# PSU-Board-V2-0.net
KiCad netlist of a schematic drawn in EAGLE
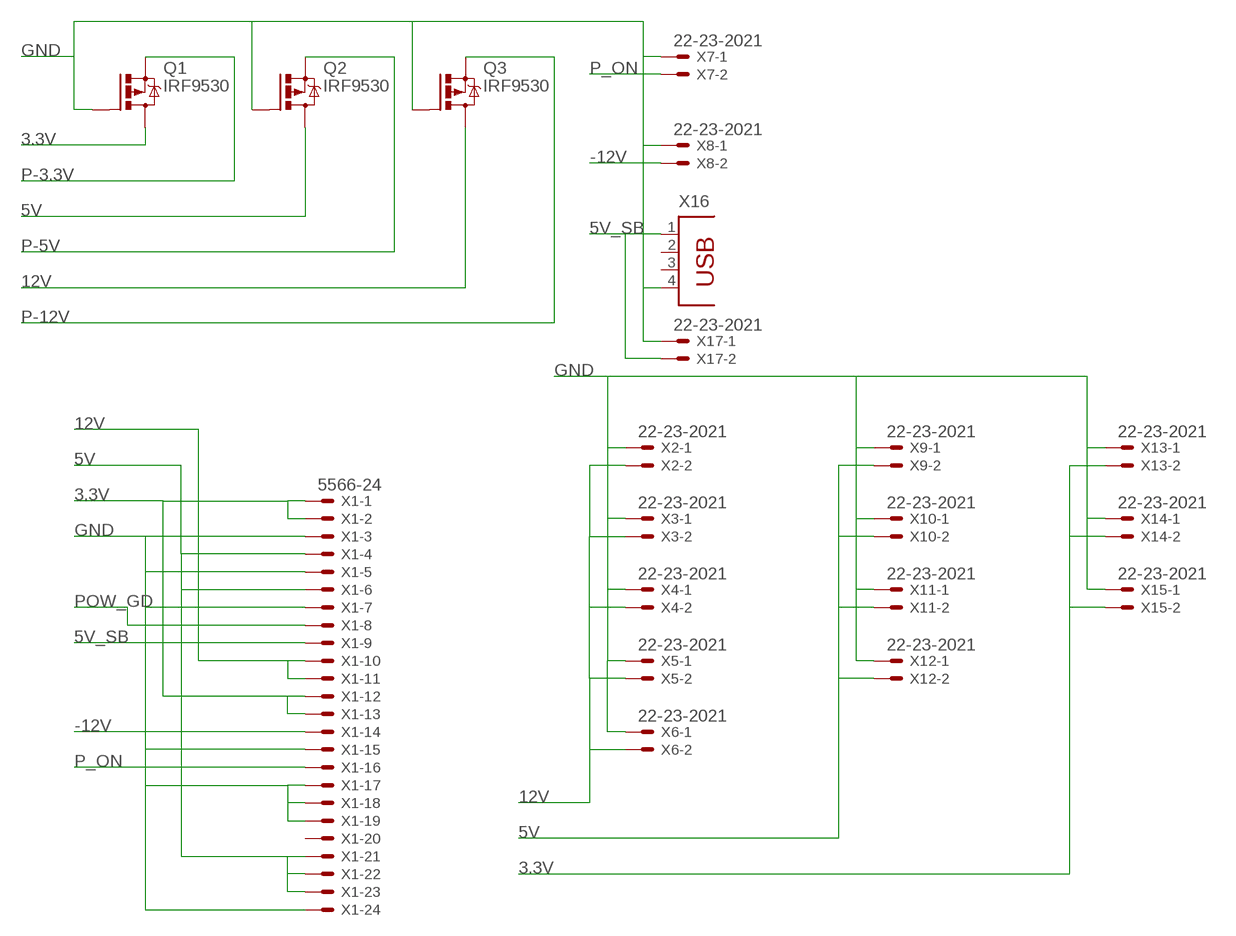
[diagram p0: schematic, sheet 1]

(export (version "E")
  (design (tool "Eeschema 10.0.6"))
  (components
    (comp (ref "Q1")
      (value "IRF9530")
      (footprint "eagle-import:TO220BV")
      (libsource (lib "eagle-import") (part "IRF9530"))
    )
    (comp (ref "Q2")
      (value "IRF9530")
      (footprint "eagle-import:TO220BV")
      (libsource (lib "eagle-import") (part "IRF9530"))
    )
    (comp (ref "Q3")
      (value "IRF9530")
      (footprint "eagle-import:TO220BV")
      (libsource (lib "eagle-import") (part "IRF9530"))
    )
    (comp (ref "X1")
      (value "5566-24")
      (footprint "eagle-import:5566-24")
      (libsource (lib "eagle-import") (part "5566-24"))
    )
    (comp (ref "X2")
      (value "22-23-2021")
      (footprint "eagle-import:22-23-2021")
      (fields (field (name "MF") "MOLEX"))
      (libsource (lib "eagle-import") (part "22-23-2021"))
    )
    (comp (ref "X3")
      (value "22-23-2021")
      (footprint "eagle-import:22-23-2021")
      (fields (field (name "MF") "MOLEX"))
      (libsource (lib "eagle-import") (part "22-23-2021"))
    )
    (comp (ref "X4")
      (value "22-23-2021")
      (footprint "eagle-import:22-23-2021")
      (fields (field (name "MF") "MOLEX"))
      (libsource (lib "eagle-import") (part "22-23-2021"))
    )
    (comp (ref "X5")
      (value "22-23-2021")
      (footprint "eagle-import:22-23-2021")
      (fields (field (name "MF") "MOLEX"))
      (libsource (lib "eagle-import") (part "22-23-2021"))
    )
    (comp (ref "X6")
      (value "22-23-2021")
      (footprint "eagle-import:22-23-2021")
      (fields (field (name "MF") "MOLEX"))
      (libsource (lib "eagle-import") (part "22-23-2021"))
    )
    (comp (ref "X7")
      (value "22-23-2021")
      (footprint "eagle-import:22-23-2021")
      (fields (field (name "MF") "MOLEX"))
      (libsource (lib "eagle-import") (part "22-23-2021"))
    )
    (comp (ref "X8")
      (value "22-23-2021")
      (footprint "eagle-import:22-23-2021")
      (fields (field (name "MF") "MOLEX"))
      (libsource (lib "eagle-import") (part "22-23-2021"))
    )
    (comp (ref "X9")
      (value "22-23-2021")
      (footprint "eagle-import:22-23-2021")
      (fields (field (name "MF") "MOLEX"))
      (libsource (lib "eagle-import") (part "22-23-2021"))
    )
    (comp (ref "X10")
      (value "22-23-2021")
      (footprint "eagle-import:22-23-2021")
      (fields (field (name "MF") "MOLEX"))
      (libsource (lib "eagle-import") (part "22-23-2021"))
    )
    (comp (ref "X11")
      (value "22-23-2021")
      (footprint "eagle-import:22-23-2021")
      (fields (field (name "MF") "MOLEX"))
      (libsource (lib "eagle-import") (part "22-23-2021"))
    )
    (comp (ref "X12")
      (value "22-23-2021")
      (footprint "eagle-import:22-23-2021")
      (fields (field (name "MF") "MOLEX"))
      (libsource (lib "eagle-import") (part "22-23-2021"))
    )
    (comp (ref "X13")
      (value "22-23-2021")
      (footprint "eagle-import:22-23-2021")
      (fields (field (name "MF") "MOLEX"))
      (libsource (lib "eagle-import") (part "22-23-2021"))
    )
    (comp (ref "X14")
      (value "22-23-2021")
      (footprint "eagle-import:22-23-2021")
      (fields (field (name "MF") "MOLEX"))
      (libsource (lib "eagle-import") (part "22-23-2021"))
    )
    (comp (ref "X15")
      (value "22-23-2021")
      (footprint "eagle-import:22-23-2021")
      (fields (field (name "MF") "MOLEX"))
      (libsource (lib "eagle-import") (part "22-23-2021"))
    )
    (comp (ref "X16")
      (value "PN87520")
      (footprint "eagle-import:PN87520")
      (libsource (lib "eagle-import") (part "PN87520"))
    )
    (comp (ref "X17")
      (value "22-23-2021")
      (footprint "eagle-import:22-23-2021")
      (fields (field (name "MF") "MOLEX"))
      (libsource (lib "eagle-import") (part "22-23-2021"))
    )
  )
  (nets
    (net (code "1") (name "/-12V") (class "Default")
      (node (ref "X1") (pin "14") (pinfunction "S_14") (pintype "passive"))
      (node (ref "X8") (pin "2") (pinfunction "S_2") (pintype "passive"))
    )
    (net (code "2") (name "/3.3V") (class "Default")
      (node (ref "Q1") (pin "D") (pinfunction "D_D") (pintype "passive"))
      (node (ref "X1") (pin "1") (pinfunction "S_1") (pintype "passive"))
      (node (ref "X1") (pin "12") (pinfunction "S_12") (pintype "passive"))
      (node (ref "X1") (pin "13") (pinfunction "S_13") (pintype "passive"))
      (node (ref "X1") (pin "2") (pinfunction "S_2") (pintype "passive"))
      (node (ref "X13") (pin "2") (pinfunction "S_2") (pintype "passive"))
      (node (ref "X14") (pin "2") (pinfunction "S_2") (pintype "passive"))
      (node (ref "X15") (pin "2") (pinfunction "S_2") (pintype "passive"))
    )
    (net (code "3") (name "/5V") (class "Default")
      (node (ref "Q2") (pin "D") (pinfunction "D_D") (pintype "passive"))
      (node (ref "X1") (pin "21") (pinfunction "S_21") (pintype "passive"))
      (node (ref "X1") (pin "22") (pinfunction "S_22") (pintype "passive"))
      (node (ref "X1") (pin "23") (pinfunction "S_23") (pintype "passive"))
      (node (ref "X1") (pin "4") (pinfunction "S_4") (pintype "passive"))
      (node (ref "X1") (pin "6") (pinfunction "S_6") (pintype "passive"))
      (node (ref "X10") (pin "2") (pinfunction "S_2") (pintype "passive"))
      (node (ref "X11") (pin "2") (pinfunction "S_2") (pintype "passive"))
      (node (ref "X12") (pin "2") (pinfunction "S_2") (pintype "passive"))
      (node (ref "X9") (pin "2") (pinfunction "S_2") (pintype "passive"))
    )
    (net (code "4") (name "/5V_SB") (class "Default")
      (node (ref "X1") (pin "9") (pinfunction "S_9") (pintype "passive"))
      (node (ref "X16") (pin "1") (pinfunction "1_1") (pintype "passive"))
      (node (ref "X17") (pin "2") (pinfunction "S_2") (pintype "passive"))
    )
    (net (code "5") (name "/12V") (class "Default")
      (node (ref "Q3") (pin "D") (pinfunction "D_D") (pintype "passive"))
      (node (ref "X1") (pin "10") (pinfunction "S_10") (pintype "passive"))
      (node (ref "X1") (pin "11") (pinfunction "S_11") (pintype "passive"))
      (node (ref "X2") (pin "2") (pinfunction "S_2") (pintype "passive"))
      (node (ref "X3") (pin "2") (pinfunction "S_2") (pintype "passive"))
      (node (ref "X4") (pin "2") (pinfunction "S_2") (pintype "passive"))
      (node (ref "X5") (pin "2") (pinfunction "S_2") (pintype "passive"))
      (node (ref "X6") (pin "2") (pinfunction "S_2") (pintype "passive"))
    )
    (net (code "6") (name "/GND") (class "Default")
      (node (ref "Q1") (pin "G") (pinfunction "G_G") (pintype "passive"))
      (node (ref "Q2") (pin "G") (pinfunction "G_G") (pintype "passive"))
      (node (ref "Q3") (pin "G") (pinfunction "G_G") (pintype "passive"))
      (node (ref "X1") (pin "15") (pinfunction "S_15") (pintype "passive"))
      (node (ref "X1") (pin "17") (pinfunction "S_17") (pintype "passive"))
      (node (ref "X1") (pin "18") (pinfunction "S_18") (pintype "passive"))
      (node (ref "X1") (pin "19") (pinfunction "S_19") (pintype "passive"))
      (node (ref "X1") (pin "24") (pinfunction "S_24") (pintype "passive"))
      (node (ref "X1") (pin "3") (pinfunction "S_3") (pintype "passive"))
      (node (ref "X1") (pin "5") (pinfunction "S_5") (pintype "passive"))
      (node (ref "X1") (pin "7") (pinfunction "S_7") (pintype "passive"))
      (node (ref "X10") (pin "1") (pinfunction "S_1") (pintype "passive"))
      (node (ref "X11") (pin "1") (pinfunction "S_1") (pintype "passive"))
      (node (ref "X12") (pin "1") (pinfunction "S_1") (pintype "passive"))
      (node (ref "X13") (pin "1") (pinfunction "S_1") (pintype "passive"))
      (node (ref "X14") (pin "1") (pinfunction "S_1") (pintype "passive"))
      (node (ref "X15") (pin "1") (pinfunction "S_1") (pintype "passive"))
      (node (ref "X16") (pin "4") (pinfunction "4_4") (pintype "passive"))
      (node (ref "X17") (pin "1") (pinfunction "S_1") (pintype "passive"))
      (node (ref "X2") (pin "1") (pinfunction "S_1") (pintype "passive"))
      (node (ref "X3") (pin "1") (pinfunction "S_1") (pintype "passive"))
      (node (ref "X4") (pin "1") (pinfunction "S_1") (pintype "passive"))
      (node (ref "X5") (pin "1") (pinfunction "S_1") (pintype "passive"))
      (node (ref "X6") (pin "1") (pinfunction "S_1") (pintype "passive"))
      (node (ref "X7") (pin "1") (pinfunction "S_1") (pintype "passive"))
      (node (ref "X8") (pin "1") (pinfunction "S_1") (pintype "passive"))
      (node (ref "X9") (pin "1") (pinfunction "S_1") (pintype "passive"))
    )
    (net (code "7") (name "/P-3.3V") (class "Default")
      (node (ref "Q1") (pin "S") (pinfunction "S_S") (pintype "passive"))
    )
    (net (code "8") (name "/P-5V") (class "Default")
      (node (ref "Q2") (pin "S") (pinfunction "S_S") (pintype "passive"))
    )
    (net (code "9") (name "/P-12V") (class "Default")
      (node (ref "Q3") (pin "S") (pinfunction "S_S") (pintype "passive"))
    )
    (net (code "10") (name "/POW_GD") (class "Default")
      (node (ref "X1") (pin "8") (pinfunction "S_8") (pintype "passive"))
    )
    (net (code "11") (name "/P_ON") (class "Default")
      (node (ref "X1") (pin "16") (pinfunction "S_16") (pintype "passive"))
      (node (ref "X7") (pin "2") (pinfunction "S_2") (pintype "passive"))
    )
    (net (code "12") (name "unconnected-(X1M-S-Pad20)") (class "Default")
      (node (ref "X1") (pin "20") (pinfunction "S_20") (pintype "passive"))
    )
    (net (code "13") (name "unconnected-(X16-Pad2)") (class "Default")
      (node (ref "X16") (pin "2") (pinfunction "2_2") (pintype "passive"))
    )
    (net (code "14") (name "unconnected-(X16-Pad3)") (class "Default")
      (node (ref "X16") (pin "3") (pinfunction "3_3") (pintype "passive"))
    )
  )
)
